# TPS54531.net
KiCad netlist of a schematic drawn in Altium Designer
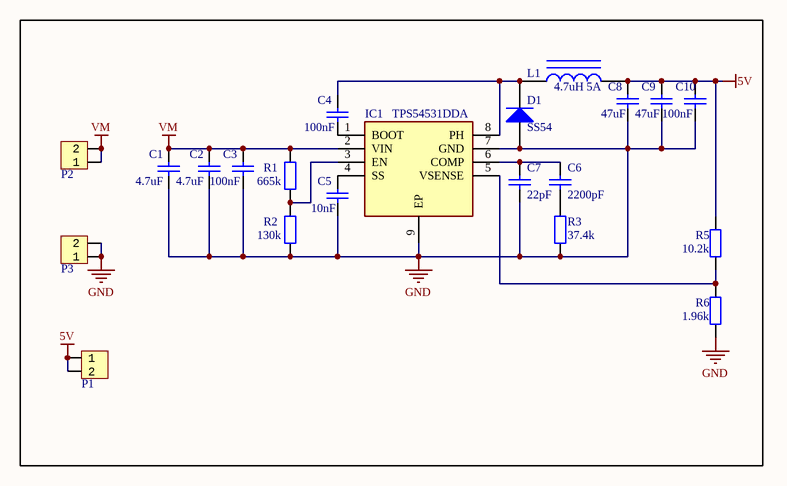
[diagram p0: TPS54531.SchDoc]

(export (version "E")
  (design (tool "Eeschema 10.0.6"))
  (components
    (comp (ref "C1")
      (value "4.7uF")
      (footprint "CAP-0603")
      (description "贴片电容")
      (libsource (lib "Power_Lib_Altium") (part "CAP"))
    )
    (comp (ref "C2")
      (value "4.7uF")
      (footprint "CAP-0603")
      (description "贴片电容")
      (libsource (lib "Power_Lib_Altium") (part "CAP"))
    )
    (comp (ref "C3")
      (value "100nF")
      (footprint "CAP-0603")
      (description "贴片电容")
      (libsource (lib "Power_Lib_Altium") (part "CAP"))
    )
    (comp (ref "C4")
      (value "100nF")
      (footprint "CAP-0603")
      (description "贴片电容")
      (libsource (lib "Power_Lib_Altium") (part "CAP"))
    )
    (comp (ref "C5")
      (value "10nF")
      (footprint "CAP-0603")
      (description "贴片电容")
      (libsource (lib "Power_Lib_Altium") (part "CAP"))
    )
    (comp (ref "C6")
      (value "2200pF")
      (footprint "CAP-0603")
      (description "贴片电容")
      (libsource (lib "Power_Lib_Altium") (part "CAP"))
    )
    (comp (ref "C7")
      (value "22pF")
      (footprint "CAP-0603")
      (description "贴片电容")
      (libsource (lib "Power_Lib_Altium") (part "CAP"))
    )
    (comp (ref "C8")
      (value "47uF")
      (footprint "CAP-0603")
      (description "贴片电容")
      (libsource (lib "Power_Lib_Altium") (part "CAP"))
    )
    (comp (ref "C9")
      (value "47uF")
      (footprint "CAP-0603")
      (description "贴片电容")
      (libsource (lib "Power_Lib_Altium") (part "CAP"))
    )
    (comp (ref "C10")
      (value "100nF")
      (footprint "CAP-0603")
      (description "贴片电容")
      (libsource (lib "Power_Lib_Altium") (part "CAP"))
    )
    (comp (ref "D1")
      (value "SS54")
      (footprint "DO-214AA/SMB")
      (description "肖特基二极管")
      (libsource (lib "Power_Lib_Altium") (part "DIODE"))
    )
    (comp (ref "IC1")
      (value "TPS54531DDA")
      (footprint "SOIC_8_PAD")
      (description "集成稳压芯片")
      (fields (field (name "MOUSER PART NUMBER") "595-TPS54531DDA"))
      (libsource (lib "Power_Lib_Altium") (part "TPS54531DDA"))
    )
    (comp (ref "L1")
      (value "4.7uH 5A")
      (footprint "L-10040")
      (description "电感")
      (libsource (lib "Power_Lib_Altium") (part "INDUCTOR"))
    )
    (comp (ref "P1")
      (value "HDR1x2_2.54")
      (footprint "HDR1X2_2.54_180")
      (description "Header")
      (libsource (lib "") (part "HDR1x2_2.54_1"))
    )
    (comp (ref "P2")
      (value "HDR1x2_2.54")
      (footprint "HDR1X2_2.54_180")
      (description "Header")
      (libsource (lib "Power_Lib_Altium") (part "HDR1x2_2.54"))
    )
    (comp (ref "P3")
      (value "HDR1x2_2.54")
      (footprint "HDR1X2_2.54_180")
      (description "Header")
      (libsource (lib "Power_Lib_Altium") (part "HDR1x2_2.54"))
    )
    (comp (ref "R1")
      (value "665k")
      (footprint "R-0603")
      (description "贴片电阻")
      (libsource (lib "Power_Lib_Altium") (part "RES"))
    )
    (comp (ref "R2")
      (value "130k")
      (footprint "R-0603")
      (description "贴片电阻")
      (libsource (lib "Power_Lib_Altium") (part "RES"))
    )
    (comp (ref "R3")
      (value "37.4k")
      (footprint "R-0603")
      (description "贴片电阻")
      (libsource (lib "Power_Lib_Altium") (part "RES"))
    )
    (comp (ref "R5")
      (value "10.2k")
      (footprint "R-0603")
      (description "贴片电阻")
      (libsource (lib "Power_Lib_Altium") (part "RES"))
    )
    (comp (ref "R6")
      (value "1.96k")
      (footprint "R-0603")
      (description "贴片电阻")
      (libsource (lib "Power_Lib_Altium") (part "RES"))
    )
  )
  (nets
    (net (code "1") (name "5V") (class "Default")
      (node (ref "C10") (pin "2") (pinfunction "2_2") (pintype "passive"))
      (node (ref "C8") (pin "2") (pinfunction "2_2") (pintype "passive"))
      (node (ref "C9") (pin "2") (pinfunction "2_2") (pintype "passive"))
      (node (ref "L1") (pin "2") (pinfunction "2_2") (pintype "passive"))
      (node (ref "P1") (pin "1") (pinfunction "1_1") (pintype "passive"))
      (node (ref "P1") (pin "2") (pinfunction "2_2") (pintype "passive"))
      (node (ref "R5") (pin "2") (pinfunction "2_2") (pintype "passive"))
    )
    (net (code "2") (name "GND") (class "Default")
      (node (ref "C1") (pin "1") (pinfunction "1_1") (pintype "passive"))
      (node (ref "C10") (pin "1") (pinfunction "1_1") (pintype "passive"))
      (node (ref "C2") (pin "1") (pinfunction "1_1") (pintype "passive"))
      (node (ref "C3") (pin "1") (pinfunction "1_1") (pintype "passive"))
      (node (ref "C5") (pin "1") (pinfunction "1_1") (pintype "passive"))
      (node (ref "C7") (pin "1") (pinfunction "1_1") (pintype "passive"))
      (node (ref "C8") (pin "1") (pinfunction "1_1") (pintype "passive"))
      (node (ref "C9") (pin "1") (pinfunction "1_1") (pintype "passive"))
      (node (ref "D1") (pin "1") (pinfunction "A_1") (pintype "passive"))
      (node (ref "IC1") (pin "7") (pinfunction "GND_7") (pintype "passive"))
      (node (ref "IC1") (pin "9") (pinfunction "EP_9") (pintype "passive"))
      (node (ref "P3") (pin "1") (pinfunction "1_1") (pintype "passive"))
      (node (ref "P3") (pin "2") (pinfunction "2_2") (pintype "passive"))
      (node (ref "R2") (pin "1") (pinfunction "1_1") (pintype "passive"))
      (node (ref "R3") (pin "1") (pinfunction "1_1") (pintype "passive"))
      (node (ref "R6") (pin "1") (pinfunction "1_1") (pintype "passive"))
    )
    (net (code "3") (name "Net-(C6-Pad1)") (class "Default")
      (node (ref "C6") (pin "1") (pinfunction "1_1") (pintype "passive"))
      (node (ref "R3") (pin "2") (pinfunction "2_2") (pintype "passive"))
    )
    (net (code "4") (name "Net-(D1-K)") (class "Default")
      (node (ref "C4") (pin "2") (pinfunction "2_2") (pintype "passive"))
      (node (ref "D1") (pin "2") (pinfunction "K_2") (pintype "passive"))
      (node (ref "IC1") (pin "8") (pinfunction "PH_8") (pintype "passive"))
      (node (ref "L1") (pin "1") (pinfunction "1_1") (pintype "passive"))
    )
    (net (code "5") (name "Net-(IC1-BOOT)") (class "Default")
      (node (ref "C4") (pin "1") (pinfunction "1_1") (pintype "passive"))
      (node (ref "IC1") (pin "1") (pinfunction "BOOT_1") (pintype "passive"))
    )
    (net (code "6") (name "Net-(IC1-COMP)") (class "Default")
      (node (ref "C6") (pin "2") (pinfunction "2_2") (pintype "passive"))
      (node (ref "C7") (pin "2") (pinfunction "2_2") (pintype "passive"))
      (node (ref "IC1") (pin "6") (pinfunction "COMP_6") (pintype "passive"))
    )
    (net (code "7") (name "Net-(IC1-EN)") (class "Default")
      (node (ref "IC1") (pin "3") (pinfunction "EN_3") (pintype "passive"))
      (node (ref "R1") (pin "1") (pinfunction "1_1") (pintype "passive"))
      (node (ref "R2") (pin "2") (pinfunction "2_2") (pintype "passive"))
    )
    (net (code "8") (name "Net-(IC1-SS)") (class "Default")
      (node (ref "C5") (pin "2") (pinfunction "2_2") (pintype "passive"))
      (node (ref "IC1") (pin "4") (pinfunction "SS_4") (pintype "passive"))
    )
    (net (code "9") (name "Net-(IC1-VSENSE)") (class "Default")
      (node (ref "IC1") (pin "5") (pinfunction "VSENSE_5") (pintype "passive"))
      (node (ref "R5") (pin "1") (pinfunction "1_1") (pintype "passive"))
      (node (ref "R6") (pin "2") (pinfunction "2_2") (pintype "passive"))
    )
    (net (code "10") (name "VM") (class "Default")
      (node (ref "C1") (pin "2") (pinfunction "2_2") (pintype "passive"))
      (node (ref "C2") (pin "2") (pinfunction "2_2") (pintype "passive"))
      (node (ref "C3") (pin "2") (pinfunction "2_2") (pintype "passive"))
      (node (ref "IC1") (pin "2") (pinfunction "VIN_2") (pintype "passive"))
      (node (ref "P2") (pin "1") (pinfunction "1_1") (pintype "passive"))
      (node (ref "P2") (pin "2") (pinfunction "2_2") (pintype "passive"))
      (node (ref "R1") (pin "2") (pinfunction "2_2") (pintype "passive"))
    )
  )
)
